# board.net
KiCad netlist of a schematic drawn in EAGLE
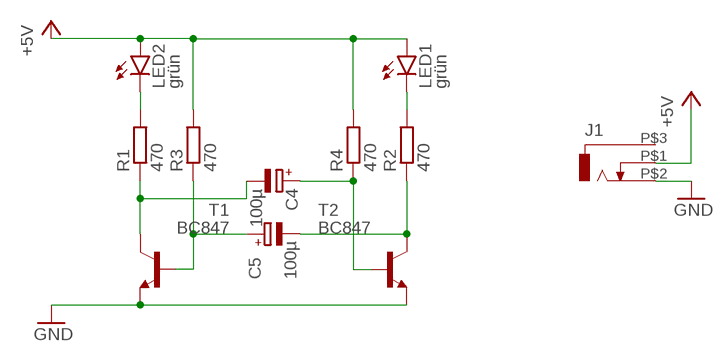
[diagram p0: schematic, sheet 1]

(export (version "E")
  (design (tool "Eeschema 10.0.6"))
  (components
    (comp (ref "C4")
      (value "100µ")
      (footprint "eagle-import:153CLV-0605")
      (libsource (lib "eagle-import") (part "CPOL-EU153CLV-0605"))
    )
    (comp (ref "C5")
      (value "100µ")
      (footprint "eagle-import:153CLV-0605")
      (libsource (lib "eagle-import") (part "CPOL-EU153CLV-0605"))
    )
    (comp (ref "J1")
      (value "RASM7X2")
      (footprint "eagle-import:RASM7X2")
      (libsource (lib "eagle-import") (part "RASM7X2"))
    )
    (comp (ref "LED1")
      (value "grün")
      (footprint "eagle-import:CHIPLED_0805")
      (libsource (lib "eagle-import") (part "LEDCHIPLED_0805"))
    )
    (comp (ref "LED2")
      (value "grün")
      (footprint "eagle-import:CHIPLED_0805")
      (libsource (lib "eagle-import") (part "LEDCHIPLED_0805"))
    )
    (comp (ref "R1")
      (value "470")
      (footprint "eagle-import:R0805")
      (libsource (lib "eagle-import") (part "R-EU_R0805"))
    )
    (comp (ref "R2")
      (value "470")
      (footprint "eagle-import:R0805")
      (libsource (lib "eagle-import") (part "R-EU_R0805"))
    )
    (comp (ref "R3")
      (value "470")
      (footprint "eagle-import:R0805")
      (libsource (lib "eagle-import") (part "R-EU_R0805"))
    )
    (comp (ref "R4")
      (value "470")
      (footprint "eagle-import:R0805")
      (libsource (lib "eagle-import") (part "R-EU_R0805"))
    )
    (comp (ref "T1")
      (value "BC847")
      (footprint "eagle-import:SOT23")
      (libsource (lib "eagle-import") (part "BC847"))
    )
    (comp (ref "T2")
      (value "BC847")
      (footprint "eagle-import:SOT23")
      (libsource (lib "eagle-import") (part "BC847"))
    )
  )
  (nets
    (net (code "1") (name "+5V") (class "Default")
      (node (ref "J1") (pin "P$1") (pinfunction "2_P$1") (pintype "passive"))
      (node (ref "LED1") (pin "A") (pinfunction "A_A") (pintype "passive"))
      (node (ref "LED2") (pin "A") (pinfunction "A_A") (pintype "passive"))
      (node (ref "R3") (pin "2") (pinfunction "2_2") (pintype "passive"))
      (node (ref "R4") (pin "2") (pinfunction "2_2") (pintype "passive"))
    )
    (net (code "2") (name "GND") (class "Default")
      (node (ref "J1") (pin "P$2") (pinfunction "3_P$2") (pintype "passive"))
      (node (ref "T1") (pin "2") (pinfunction "E_2") (pintype "passive"))
      (node (ref "T2") (pin "2") (pinfunction "E_2") (pintype "passive"))
    )
    (net (code "3") (name "Net-(LED1-PadC)") (class "Default")
      (node (ref "LED1") (pin "C") (pinfunction "C_C") (pintype "passive"))
      (node (ref "R2") (pin "2") (pinfunction "2_2") (pintype "passive"))
    )
    (net (code "4") (name "Net-(LED2-PadC)") (class "Default")
      (node (ref "LED2") (pin "C") (pinfunction "C_C") (pintype "passive"))
      (node (ref "R1") (pin "2") (pinfunction "2_2") (pintype "passive"))
    )
    (net (code "5") (name "Net-(T1-B)") (class "Default")
      (node (ref "C5") (pin "+") (pinfunction "+_+") (pintype "passive"))
      (node (ref "R3") (pin "1") (pinfunction "1_1") (pintype "passive"))
      (node (ref "T1") (pin "1") (pinfunction "B_1") (pintype "passive"))
    )
    (net (code "6") (name "Net-(T1-C)") (class "Default")
      (node (ref "C4") (pin "-") (pinfunction "-_-") (pintype "passive"))
      (node (ref "R1") (pin "1") (pinfunction "1_1") (pintype "passive"))
      (node (ref "T1") (pin "3") (pinfunction "C_3") (pintype "passive"))
    )
    (net (code "7") (name "Net-(T2-B)") (class "Default")
      (node (ref "C4") (pin "+") (pinfunction "+_+") (pintype "passive"))
      (node (ref "R4") (pin "1") (pinfunction "1_1") (pintype "passive"))
      (node (ref "T2") (pin "1") (pinfunction "B_1") (pintype "passive"))
    )
    (net (code "8") (name "Net-(T2-C)") (class "Default")
      (node (ref "C5") (pin "-") (pinfunction "-_-") (pintype "passive"))
      (node (ref "R2") (pin "1") (pinfunction "1_1") (pintype "passive"))
      (node (ref "T2") (pin "3") (pinfunction "C_3") (pintype "passive"))
    )
    (net (code "9") (name "unconnected-(J1-1-PadP$3)") (class "Default")
      (node (ref "J1") (pin "P$3") (pinfunction "1_P$3") (pintype "passive"))
    )
  )
)
